# ESP32.net
KiCad netlist of a schematic drawn in Altium Designer
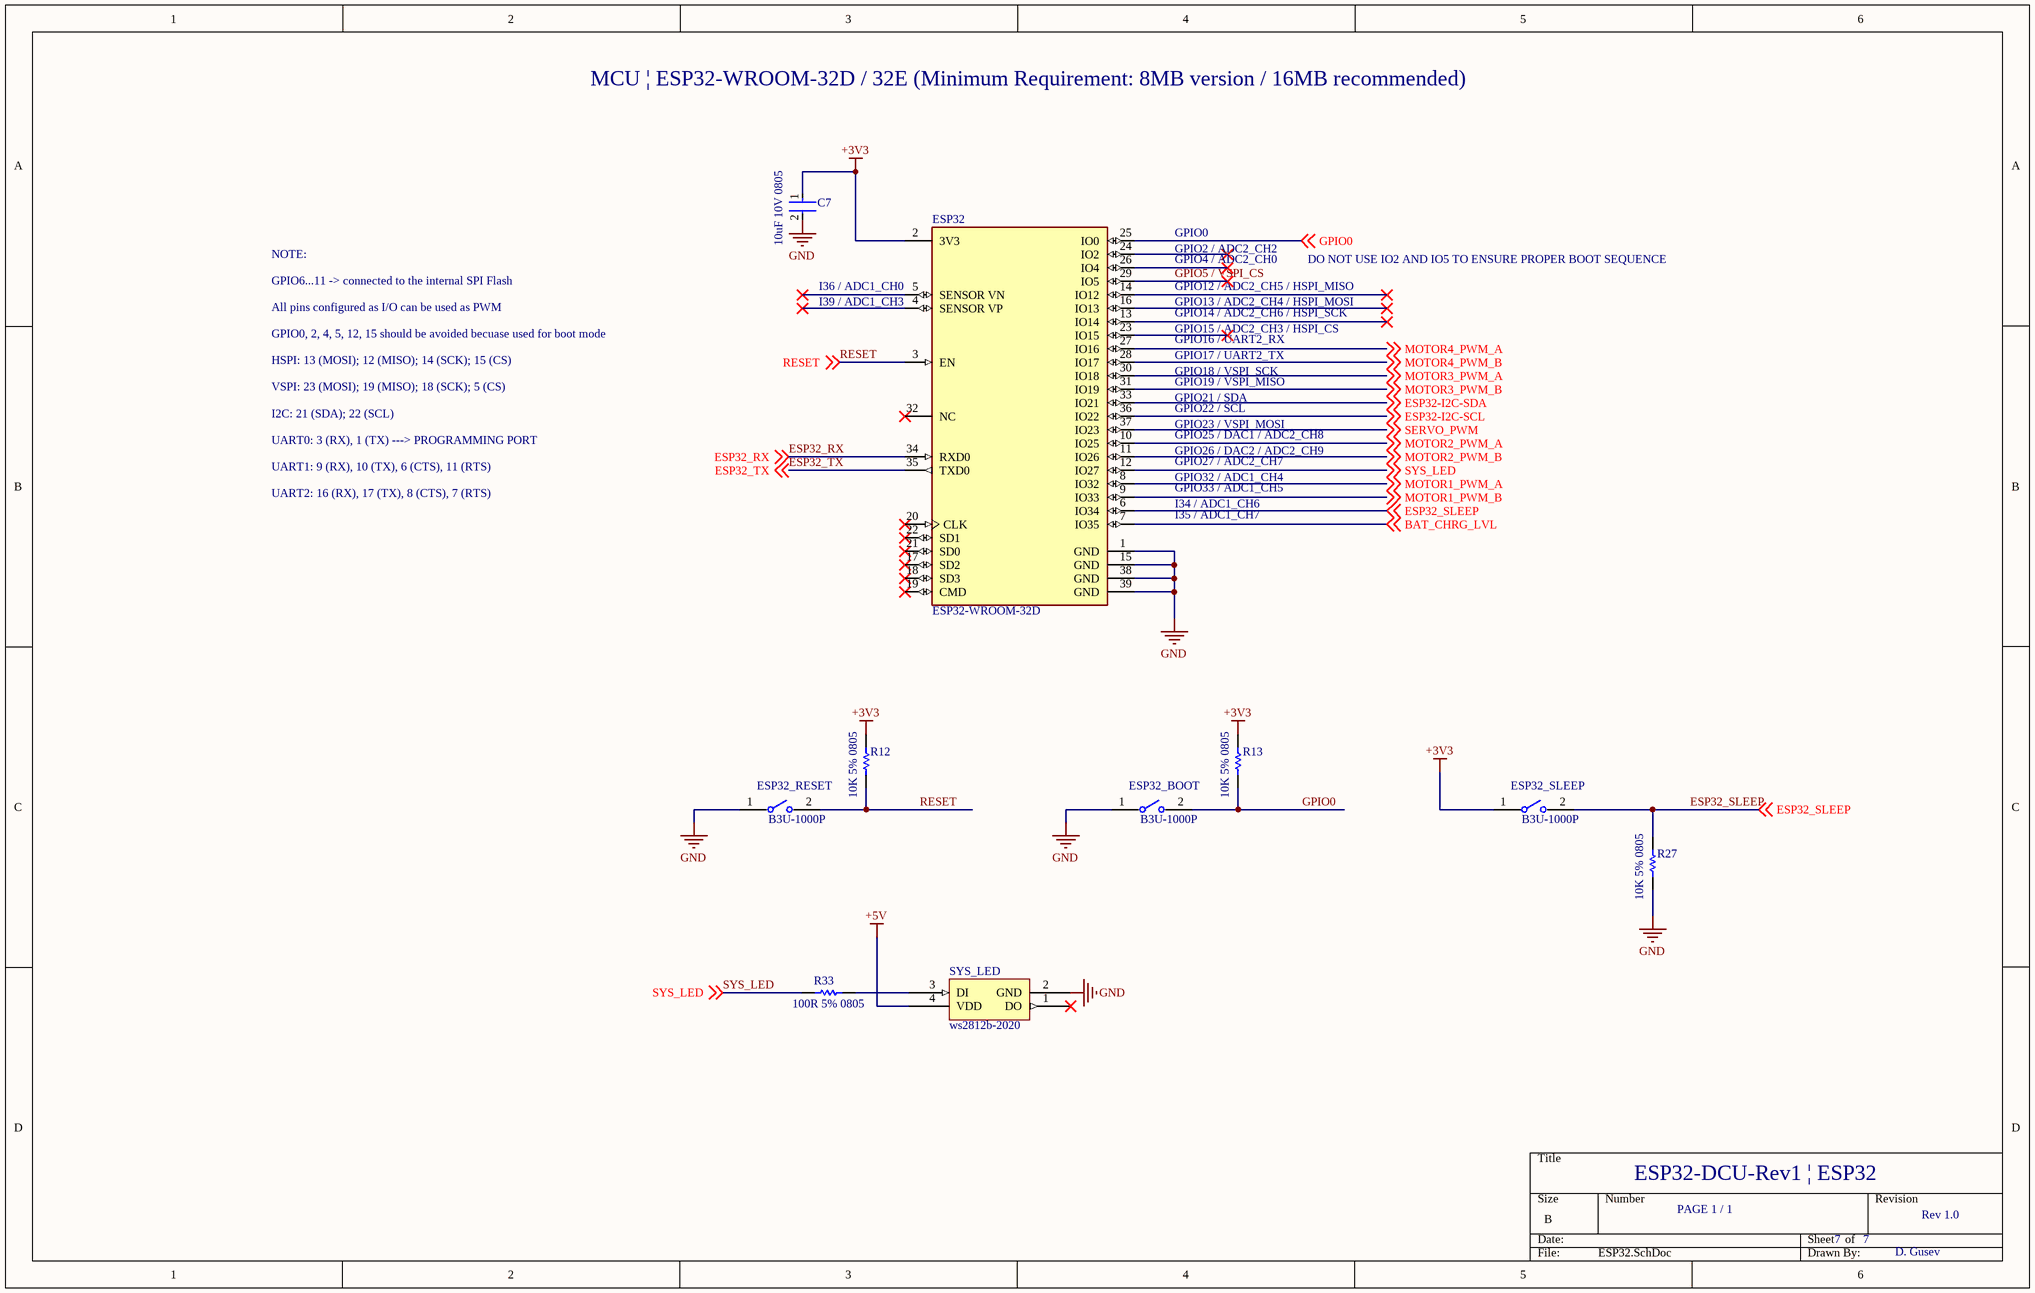
[diagram p0: ESP32.SchDoc]

(export (version "E")
  (design (tool "Eeschema 10.0.6"))
  (components
    (comp (ref "C7")
      (value "10uF 10V 0805")
      (footprint "FP-C0805C-DG-MFG")
      (description "CAP CER 10UF 10V X5R 0805")
      (fields (field (name "TOLERANCE") "10%") (field (name "MANUFACTURER PART NUMBER") "C0805C106K8PACTU"))
      (libsource (lib "Altium Content Vault") (part "11868f565c42a9108669ba33697ecf6"))
    )
    (comp (ref "ESP32")
      (value "ESP32-WROOM-32D")
      (footprint "ESP32-WROOM-U")
      (description "WIFI MODULE 32MBITS SPI FLASH")
      (fields
        (field (name "OCTOPART") "https://octopart.com/esp32-wroom-32d-espressif+systems-91040050")
        (field (name "MANUFACTURER") "Espressif Systems")
      )
      (libsource (lib "ddrlegobrick") (part "ESP32-WROOM-U"))
    )
    (comp (ref "ESP32_BOOT")
      (value "B3U-1000P")
      (footprint "FP-B3U-1000P-MFG")
      (description "SWITCH TACTILE SPST-NO 0.05A 12V")
      (libsource (lib "Altium Content Vault") (part "ae622034201233ca1abcedc05908f33"))
    )
    (comp (ref "ESP32_RESET")
      (value "B3U-1000P")
      (footprint "FP-B3U-1000P-MFG")
      (description "SWITCH TACTILE SPST-NO 0.05A 12V")
      (libsource (lib "Altium Content Vault") (part "ae622034201233ca1abcedc05908f33"))
    )
    (comp (ref "ESP32_SLEEP")
      (value "B3U-1000P")
      (footprint "FP-B3U-1000P-MFG")
      (description "SWITCH TACTILE SPST-NO 0.05A 12V")
      (libsource (lib "Altium Content Vault") (part "ae622034201233ca1abcedc05908f33"))
    )
    (comp (ref "R12")
      (value "10K 5% 0805")
      (footprint "RESC2013X60X40ML20T25")
      (fields (field (name "PART NUMBER") "ERA6AEB123V") (field (name "MANUFACTURER") "Panasonic"))
      (libsource (lib "Altium Content Vault") (part "RES"))
    )
    (comp (ref "R13")
      (value "10K 5% 0805")
      (footprint "RESC2013X60X40ML20T25")
      (fields (field (name "PART NUMBER") "ERA6AEB123V") (field (name "MANUFACTURER") "Panasonic"))
      (libsource (lib "Altium Content Vault") (part "RES"))
    )
    (comp (ref "R27")
      (value "10K 5% 0805")
      (footprint "RESC2013X60X40ML20T25")
      (fields (field (name "PART NUMBER") "ERA6AEB123V") (field (name "MANUFACTURER") "Panasonic"))
      (libsource (lib "Altium Content Vault") (part "RES"))
    )
    (comp (ref "R33")
      (value "100R 5% 0805")
      (footprint "RESC2013X60X35ML10T20")
      (description "Chip Resistor, 100 Ohm, +/-1%, 0.125 W, -55 to 155 degC, 0805 (2012 Metric), RoHS, Tape and Reel")
      (fields (field (name "TOLERANCE") "1%") (field (name "MANUFACTURER") "Yageo"))
      (libsource (lib "Altium Content Vault") (part "RES-2"))
    )
    (comp (ref "SYS_LED")
      (value "ws2812b-2020")
      (footprint "ws2812b")
      (libsource (lib "ddrlegobrick") (part "ws2812b-2020"))
    )
  )
  (nets
    (net (code "1") (name "+3V3") (class "Default")
      (node (ref "C7") (pin "1") (pinfunction "1_1") (pintype "passive"))
      (node (ref "ESP32") (pin "2") (pinfunction "3V3_2") (pintype "power_in"))
      (node (ref "ESP32_SLEEP") (pin "1") (pinfunction "1_1") (pintype "passive"))
      (node (ref "R12") (pin "2") (pinfunction "2_2") (pintype "passive"))
      (node (ref "R13") (pin "2") (pinfunction "2_2") (pintype "passive"))
    )
    (net (code "2") (name "+5V") (class "Default")
      (node (ref "SYS_LED") (pin "4") (pinfunction "VDD_4") (pintype "power_in"))
    )
    (net (code "3") (name "/GPIO5 {slash} VSPI_CS") (class "Default")
      (node (ref "ESP32") (pin "29") (pinfunction "IO5_29") (pintype "bidirectional+no_connect"))
    )
    (net (code "4") (name "BAT_CHRG_LVL") (class "Default")
      (node (ref "ESP32") (pin "7") (pinfunction "IO35_7") (pintype "bidirectional"))
    )
    (net (code "5") (name "ESP32-I2C-SCL") (class "Default")
      (node (ref "ESP32") (pin "36") (pinfunction "IO22_36") (pintype "bidirectional"))
    )
    (net (code "6") (name "ESP32-I2C-SDA") (class "Default")
      (node (ref "ESP32") (pin "33") (pinfunction "IO21_33") (pintype "bidirectional"))
    )
    (net (code "7") (name "ESP32_RX") (class "Default")
      (node (ref "ESP32") (pin "34") (pinfunction "RXD0_34") (pintype "input"))
    )
    (net (code "8") (name "ESP32_SLEEP") (class "Default")
      (node (ref "ESP32") (pin "6") (pinfunction "IO34_6") (pintype "bidirectional"))
      (node (ref "ESP32_SLEEP") (pin "2") (pinfunction "2_2") (pintype "passive"))
      (node (ref "R27") (pin "2") (pinfunction "2_2") (pintype "passive"))
    )
    (net (code "9") (name "ESP32_TX") (class "Default")
      (node (ref "ESP32") (pin "35") (pinfunction "TXD0_35") (pintype "output"))
    )
    (net (code "10") (name "GND") (class "Default")
      (node (ref "C7") (pin "2") (pinfunction "2_2") (pintype "passive"))
      (node (ref "ESP32") (pin "1") (pinfunction "GND_1") (pintype "power_in"))
      (node (ref "ESP32") (pin "15") (pinfunction "GND_15") (pintype "power_in"))
      (node (ref "ESP32") (pin "38") (pinfunction "GND_38") (pintype "power_in"))
      (node (ref "ESP32") (pin "39") (pinfunction "GND_39") (pintype "power_in"))
      (node (ref "ESP32_BOOT") (pin "1") (pinfunction "1_1") (pintype "passive"))
      (node (ref "ESP32_RESET") (pin "1") (pinfunction "1_1") (pintype "passive"))
      (node (ref "R27") (pin "1") (pinfunction "1_1") (pintype "passive"))
      (node (ref "SYS_LED") (pin "2") (pinfunction "GND_2") (pintype "passive"))
    )
    (net (code "11") (name "GPIO0") (class "Default")
      (node (ref "ESP32") (pin "25") (pinfunction "IO0_25") (pintype "bidirectional"))
      (node (ref "ESP32_BOOT") (pin "2") (pinfunction "2_2") (pintype "passive"))
      (node (ref "R13") (pin "1") (pinfunction "1_1") (pintype "passive"))
    )
    (net (code "12") (name "MOTOR1_PWM_A") (class "Default")
      (node (ref "ESP32") (pin "8") (pinfunction "IO32_8") (pintype "bidirectional"))
    )
    (net (code "13") (name "MOTOR1_PWM_B") (class "Default")
      (node (ref "ESP32") (pin "9") (pinfunction "IO33_9") (pintype "bidirectional"))
    )
    (net (code "14") (name "MOTOR2_PWM_A") (class "Default")
      (node (ref "ESP32") (pin "10") (pinfunction "IO25_10") (pintype "bidirectional"))
    )
    (net (code "15") (name "MOTOR2_PWM_B") (class "Default")
      (node (ref "ESP32") (pin "11") (pinfunction "IO26_11") (pintype "bidirectional"))
    )
    (net (code "16") (name "MOTOR3_PWM_A") (class "Default")
      (node (ref "ESP32") (pin "30") (pinfunction "IO18_30") (pintype "bidirectional"))
    )
    (net (code "17") (name "MOTOR3_PWM_B") (class "Default")
      (node (ref "ESP32") (pin "31") (pinfunction "IO19_31") (pintype "bidirectional"))
    )
    (net (code "18") (name "MOTOR4_PWM_A") (class "Default")
      (node (ref "ESP32") (pin "27") (pinfunction "IO16_27") (pintype "bidirectional"))
    )
    (net (code "19") (name "MOTOR4_PWM_B") (class "Default")
      (node (ref "ESP32") (pin "28") (pinfunction "IO17_28") (pintype "bidirectional"))
    )
    (net (code "20") (name "Net-(SYS_LED-DI)") (class "Default")
      (node (ref "R33") (pin "2") (pinfunction "2_2") (pintype "passive"))
      (node (ref "SYS_LED") (pin "3") (pinfunction "DI_3") (pintype "input"))
    )
    (net (code "21") (name "RESET") (class "Default")
      (node (ref "ESP32") (pin "3") (pinfunction "EN_3") (pintype "input"))
      (node (ref "ESP32_RESET") (pin "2") (pinfunction "2_2") (pintype "passive"))
      (node (ref "R12") (pin "1") (pinfunction "1_1") (pintype "passive"))
    )
    (net (code "22") (name "SERVO_PWM") (class "Default")
      (node (ref "ESP32") (pin "37") (pinfunction "IO23_37") (pintype "bidirectional"))
    )
    (net (code "23") (name "SYS_LED") (class "Default")
      (node (ref "ESP32") (pin "12") (pinfunction "IO27_12") (pintype "bidirectional"))
      (node (ref "R33") (pin "1") (pinfunction "1_1") (pintype "passive"))
    )
    (net (code "24") (name "unconnected-(ESP32-CLK-Pad20)") (class "Default")
      (node (ref "ESP32") (pin "20") (pinfunction "CLK_20") (pintype "input+no_connect"))
    )
    (net (code "25") (name "unconnected-(ESP32-CMD-Pad19)") (class "Default")
      (node (ref "ESP32") (pin "19") (pinfunction "CMD_19") (pintype "bidirectional+no_connect"))
    )
    (net (code "26") (name "unconnected-(ESP32-IO2-Pad24)") (class "Default")
      (node (ref "ESP32") (pin "24") (pinfunction "IO2_24") (pintype "bidirectional+no_connect"))
    )
    (net (code "27") (name "unconnected-(ESP32-IO4-Pad26)") (class "Default")
      (node (ref "ESP32") (pin "26") (pinfunction "IO4_26") (pintype "bidirectional+no_connect"))
    )
    (net (code "28") (name "unconnected-(ESP32-IO12-Pad14)") (class "Default")
      (node (ref "ESP32") (pin "14") (pinfunction "IO12_14") (pintype "bidirectional+no_connect"))
    )
    (net (code "29") (name "unconnected-(ESP32-IO13-Pad16)") (class "Default")
      (node (ref "ESP32") (pin "16") (pinfunction "IO13_16") (pintype "bidirectional+no_connect"))
    )
    (net (code "30") (name "unconnected-(ESP32-IO14-Pad13)") (class "Default")
      (node (ref "ESP32") (pin "13") (pinfunction "IO14_13") (pintype "bidirectional+no_connect"))
    )
    (net (code "31") (name "unconnected-(ESP32-IO15-Pad23)") (class "Default")
      (node (ref "ESP32") (pin "23") (pinfunction "IO15_23") (pintype "bidirectional+no_connect"))
    )
    (net (code "32") (name "unconnected-(ESP32-NC-Pad32)") (class "Default")
      (node (ref "ESP32") (pin "32") (pinfunction "NC_32") (pintype "passive+no_connect"))
    )
    (net (code "33") (name "unconnected-(ESP32-SD0-Pad21)") (class "Default")
      (node (ref "ESP32") (pin "21") (pinfunction "SD0_21") (pintype "bidirectional+no_connect"))
    )
    (net (code "34") (name "unconnected-(ESP32-SD1-Pad22)") (class "Default")
      (node (ref "ESP32") (pin "22") (pinfunction "SD1_22") (pintype "bidirectional+no_connect"))
    )
    (net (code "35") (name "unconnected-(ESP32-SD2-Pad17)") (class "Default")
      (node (ref "ESP32") (pin "17") (pinfunction "SD2_17") (pintype "bidirectional+no_connect"))
    )
    (net (code "36") (name "unconnected-(ESP32-SD3-Pad18)") (class "Default")
      (node (ref "ESP32") (pin "18") (pinfunction "SD3_18") (pintype "bidirectional+no_connect"))
    )
    (net (code "37") (name "unconnected-(ESP32-SENSOR_VN-Pad5)") (class "Default")
      (node (ref "ESP32") (pin "5") (pinfunction "SENSOR_VN_5") (pintype "bidirectional+no_connect"))
    )
    (net (code "38") (name "unconnected-(ESP32-SENSOR_VP-Pad4)") (class "Default")
      (node (ref "ESP32") (pin "4") (pinfunction "SENSOR_VP_4") (pintype "bidirectional+no_connect"))
    )
    (net (code "39") (name "unconnected-(SYS_LED-DO-Pad1)") (class "Default")
      (node (ref "SYS_LED") (pin "1") (pinfunction "DO_1") (pintype "output+no_connect"))
    )
  )
)
